# 05_Mechanical.net
KiCad netlist of a schematic drawn in Altium Designer
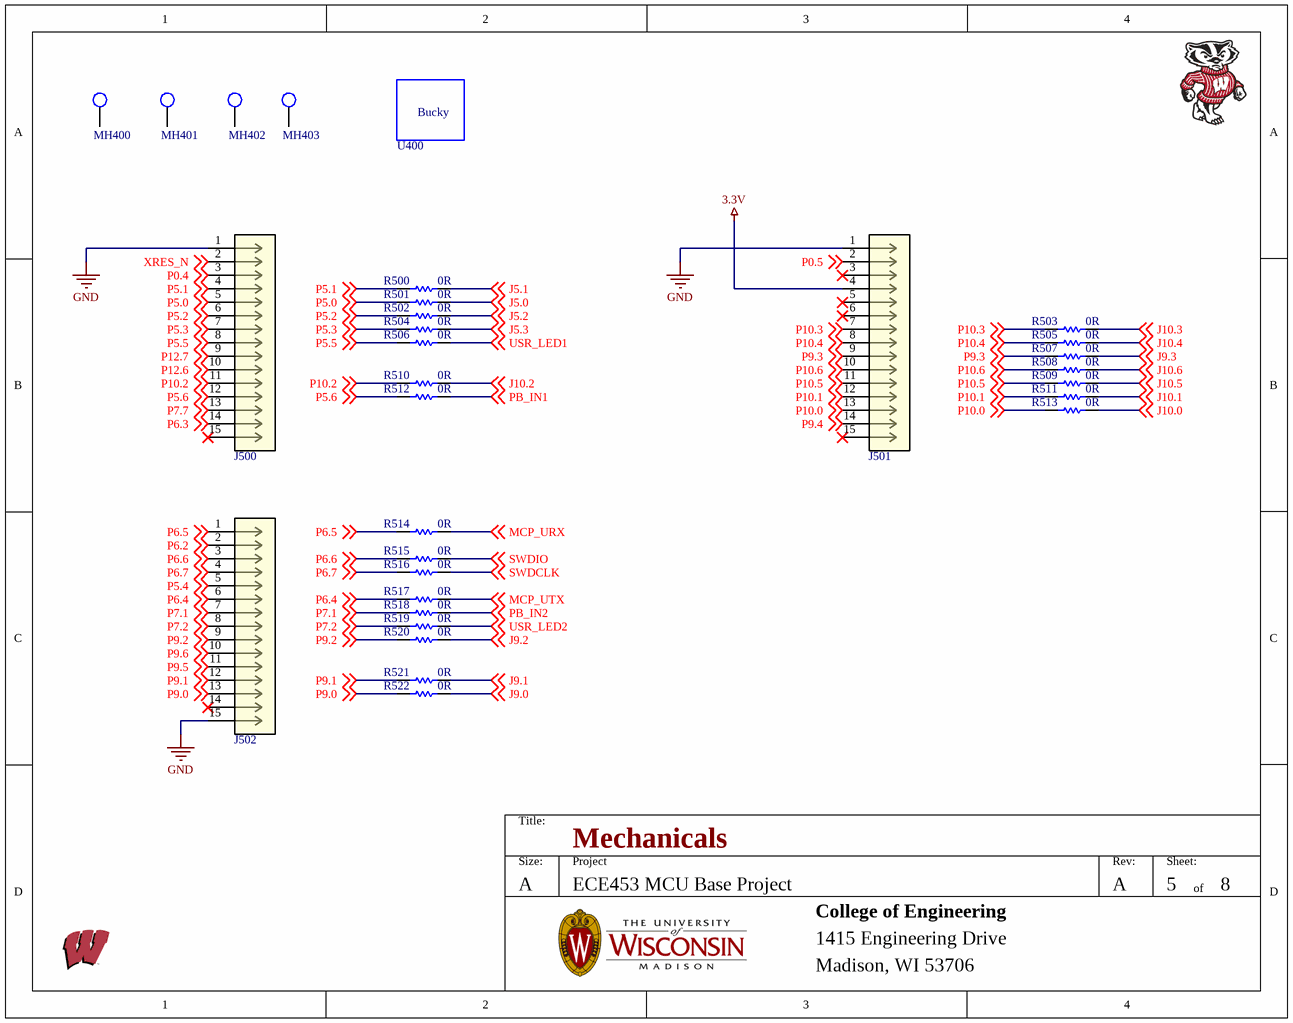
[diagram p0: 05_Mechanical.SchDoc]

(export (version "E")
  (design (tool "Eeschema 10.0.6"))
  (components
    (comp (ref "J500")
      (value "68000-115HLF")
      (footprint "CONN_15POS_2P54MM")
      (description "Conn Unshrouded Header HDR 15 POS 2.54mm Solder ST Thru-Hole")
      (fields
        (field (name "MANUFACTURER") "Adam Equipment")
        (field (name "MANUFACTURER PART NUMBER") "PH1-15-UA")
        (field (name "COPYRIGHT") "Copyright (C) 2024 Ultra Librarian. All rights reserved.")
      )
      (libsource (lib "ECE453_S24") (part "CONN_HEADER_POS_30_2.54MM"))
    )
    (comp (ref "J501")
      (value "68000-115HLF")
      (footprint "CONN_15POS_2P54MM")
      (description "Conn Unshrouded Header HDR 15 POS 2.54mm Solder ST Thru-Hole")
      (fields
        (field (name "MANUFACTURER") "Adam Equipment")
        (field (name "MANUFACTURER PART NUMBER") "PH1-15-UA")
        (field (name "COPYRIGHT") "Copyright (C) 2024 Ultra Librarian. All rights reserved.")
      )
      (libsource (lib "ECE453_S24") (part "CONN_HEADER_POS_30_2.54MM"))
    )
    (comp (ref "J502")
      (value "68000-115HLF")
      (footprint "CONN_15POS_2P54MM")
      (description "Conn Unshrouded Header HDR 15 POS 2.54mm Solder ST Thru-Hole")
      (fields
        (field (name "MANUFACTURER") "Adam Equipment")
        (field (name "MANUFACTURER PART NUMBER") "PH1-15-UA")
        (field (name "COPYRIGHT") "Copyright (C) 2024 Ultra Librarian. All rights reserved.")
      )
      (libsource (lib "ECE453_S24") (part "CONN_HEADER_POS_30_2.54MM"))
    )
    (comp (ref "MH400")
      (value "MHOLE_2_55MM")
      (footprint "MHOLE_2_55MM")
      (description "Mounting Holde")
      (fields (field (name "MANUFACTURER PART NUMBER") "UW MTHOLE"))
      (libsource (lib "ECE453_S24") (part "MHOLE_2_55MM"))
    )
    (comp (ref "MH401")
      (value "MHOLE_2_55MM")
      (footprint "MHOLE_2_55MM")
      (description "Mounting Holde")
      (fields (field (name "MANUFACTURER PART NUMBER") "UW MTHOLE"))
      (libsource (lib "ECE453_S24") (part "MHOLE_2_55MM"))
    )
    (comp (ref "MH402")
      (value "MHOLE_2_55MM")
      (footprint "MHOLE_2_55MM")
      (description "Mounting Holde")
      (fields (field (name "MANUFACTURER PART NUMBER") "UW MTHOLE"))
      (libsource (lib "ECE453_S24") (part "MHOLE_2_55MM"))
    )
    (comp (ref "MH403")
      (value "MHOLE_2_55MM")
      (footprint "MHOLE_2_55MM")
      (description "Mounting Holde")
      (fields (field (name "MANUFACTURER PART NUMBER") "UW MTHOLE"))
      (libsource (lib "ECE453_S24") (part "MHOLE_2_55MM"))
    )
    (comp (ref "R500")
      (value "0R")
      (footprint "RESC2013X70X40NL20T20")
      (description "Chip Resistor, 0 Ohm, +/- 1%, 0.125 W, -55 to 155 degC, 0805 (2012 Metric), RoHS, Tape and Reel")
      (fields (field (name "PARTNUMBER") "ERJ-6GEY0R00V") (field (name "TOLERANCE") "5%"))
      (libsource (lib "Altium Content Vault") (part "RES-2"))
    )
    (comp (ref "R501")
      (value "0R")
      (footprint "RESC2013X70X40NL20T20")
      (description "Chip Resistor, 0 Ohm, +/- 1%, 0.125 W, -55 to 155 degC, 0805 (2012 Metric), RoHS, Tape and Reel")
      (fields (field (name "PARTNUMBER") "ERJ-6GEY0R00V") (field (name "TOLERANCE") "5%"))
      (libsource (lib "Altium Content Vault") (part "RES-2"))
    )
    (comp (ref "R502")
      (value "0R")
      (footprint "RESC2013X70X40NL20T20")
      (description "Chip Resistor, 0 Ohm, +/- 1%, 0.125 W, -55 to 155 degC, 0805 (2012 Metric), RoHS, Tape and Reel")
      (fields (field (name "PARTNUMBER") "ERJ-6GEY0R00V") (field (name "TOLERANCE") "5%"))
      (libsource (lib "Altium Content Vault") (part "RES-2"))
    )
    (comp (ref "R503")
      (value "0R")
      (footprint "RESC2013X70X40NL20T20")
      (description "Chip Resistor, 0 Ohm, +/- 1%, 0.125 W, -55 to 155 degC, 0805 (2012 Metric), RoHS, Tape and Reel")
      (fields (field (name "PARTNUMBER") "ERJ-6GEY0R00V") (field (name "TOLERANCE") "5%"))
      (libsource (lib "Altium Content Vault") (part "RES-2"))
    )
    (comp (ref "R504")
      (value "0R")
      (footprint "RESC2013X70X40NL20T20")
      (description "Chip Resistor, 0 Ohm, +/- 1%, 0.125 W, -55 to 155 degC, 0805 (2012 Metric), RoHS, Tape and Reel")
      (fields (field (name "PARTNUMBER") "ERJ-6GEY0R00V") (field (name "TOLERANCE") "5%"))
      (libsource (lib "Altium Content Vault") (part "RES-2"))
    )
    (comp (ref "R505")
      (value "0R")
      (footprint "RESC2013X70X40NL20T20")
      (description "Chip Resistor, 0 Ohm, +/- 1%, 0.125 W, -55 to 155 degC, 0805 (2012 Metric), RoHS, Tape and Reel")
      (fields (field (name "PARTNUMBER") "ERJ-6GEY0R00V") (field (name "TOLERANCE") "5%"))
      (libsource (lib "Altium Content Vault") (part "RES-2"))
    )
    (comp (ref "R506")
      (value "0R")
      (footprint "RESC2013X70X40NL20T20")
      (description "Chip Resistor, 0 Ohm, +/- 1%, 0.125 W, -55 to 155 degC, 0805 (2012 Metric), RoHS, Tape and Reel")
      (fields (field (name "PARTNUMBER") "ERJ-6GEY0R00V") (field (name "TOLERANCE") "5%"))
      (libsource (lib "Altium Content Vault") (part "RES-2"))
    )
    (comp (ref "R507")
      (value "0R")
      (footprint "RESC2013X70X40NL20T20")
      (description "Chip Resistor, 0 Ohm, +/- 1%, 0.125 W, -55 to 155 degC, 0805 (2012 Metric), RoHS, Tape and Reel")
      (fields (field (name "PARTNUMBER") "ERJ-6GEY0R00V") (field (name "TOLERANCE") "5%"))
      (libsource (lib "Altium Content Vault") (part "RES-2"))
    )
    (comp (ref "R508")
      (value "0R")
      (footprint "RESC2013X70X40NL20T20")
      (description "Chip Resistor, 0 Ohm, +/- 1%, 0.125 W, -55 to 155 degC, 0805 (2012 Metric), RoHS, Tape and Reel")
      (fields (field (name "PARTNUMBER") "ERJ-6GEY0R00V") (field (name "TOLERANCE") "5%"))
      (libsource (lib "Altium Content Vault") (part "RES-2"))
    )
    (comp (ref "R509")
      (value "0R")
      (footprint "RESC2013X70X40NL20T20")
      (description "Chip Resistor, 0 Ohm, +/- 1%, 0.125 W, -55 to 155 degC, 0805 (2012 Metric), RoHS, Tape and Reel")
      (fields (field (name "PARTNUMBER") "ERJ-6GEY0R00V") (field (name "TOLERANCE") "5%"))
      (libsource (lib "Altium Content Vault") (part "RES-2"))
    )
    (comp (ref "R510")
      (value "0R")
      (footprint "RESC2013X70X40NL20T20")
      (description "Chip Resistor, 0 Ohm, +/- 1%, 0.125 W, -55 to 155 degC, 0805 (2012 Metric), RoHS, Tape and Reel")
      (fields (field (name "PARTNUMBER") "ERJ-6GEY0R00V") (field (name "TOLERANCE") "5%"))
      (libsource (lib "Altium Content Vault") (part "RES-2"))
    )
    (comp (ref "R511")
      (value "0R")
      (footprint "RESC2013X70X40NL20T20")
      (description "Chip Resistor, 0 Ohm, +/- 1%, 0.125 W, -55 to 155 degC, 0805 (2012 Metric), RoHS, Tape and Reel")
      (fields (field (name "PARTNUMBER") "ERJ-6GEY0R00V") (field (name "TOLERANCE") "5%"))
      (libsource (lib "Altium Content Vault") (part "RES-2"))
    )
    (comp (ref "R512")
      (value "0R")
      (footprint "RESC2013X70X40NL20T20")
      (description "Chip Resistor, 0 Ohm, +/- 1%, 0.125 W, -55 to 155 degC, 0805 (2012 Metric), RoHS, Tape and Reel")
      (fields (field (name "PARTNUMBER") "ERJ-6GEY0R00V") (field (name "TOLERANCE") "5%"))
      (libsource (lib "Altium Content Vault") (part "RES-2"))
    )
    (comp (ref "R513")
      (value "0R")
      (footprint "RESC2013X70X40NL20T20")
      (description "Chip Resistor, 0 Ohm, +/- 1%, 0.125 W, -55 to 155 degC, 0805 (2012 Metric), RoHS, Tape and Reel")
      (fields (field (name "PARTNUMBER") "ERJ-6GEY0R00V") (field (name "TOLERANCE") "5%"))
      (libsource (lib "Altium Content Vault") (part "RES-2"))
    )
    (comp (ref "R514")
      (value "0R")
      (footprint "RESC2013X70X40NL20T20")
      (description "Chip Resistor, 0 Ohm, +/- 1%, 0.125 W, -55 to 155 degC, 0805 (2012 Metric), RoHS, Tape and Reel")
      (fields (field (name "PARTNUMBER") "ERJ-6GEY0R00V") (field (name "TOLERANCE") "5%"))
      (libsource (lib "Altium Content Vault") (part "RES-2"))
    )
    (comp (ref "R515")
      (value "0R")
      (footprint "RESC2013X70X40NL20T20")
      (description "Chip Resistor, 0 Ohm, +/- 1%, 0.125 W, -55 to 155 degC, 0805 (2012 Metric), RoHS, Tape and Reel")
      (fields (field (name "PARTNUMBER") "ERJ-6GEY0R00V") (field (name "TOLERANCE") "5%"))
      (libsource (lib "Altium Content Vault") (part "RES-2"))
    )
    (comp (ref "R516")
      (value "0R")
      (footprint "RESC2013X70X40NL20T20")
      (description "Chip Resistor, 0 Ohm, +/- 1%, 0.125 W, -55 to 155 degC, 0805 (2012 Metric), RoHS, Tape and Reel")
      (fields (field (name "PARTNUMBER") "ERJ-6GEY0R00V") (field (name "TOLERANCE") "5%"))
      (libsource (lib "Altium Content Vault") (part "RES-2"))
    )
    (comp (ref "R517")
      (value "0R")
      (footprint "RESC2013X70X40NL20T20")
      (description "Chip Resistor, 0 Ohm, +/- 1%, 0.125 W, -55 to 155 degC, 0805 (2012 Metric), RoHS, Tape and Reel")
      (fields (field (name "PARTNUMBER") "ERJ-6GEY0R00V") (field (name "TOLERANCE") "5%"))
      (libsource (lib "Altium Content Vault") (part "RES-2"))
    )
    (comp (ref "R518")
      (value "0R")
      (footprint "RESC2013X70X40NL20T20")
      (description "Chip Resistor, 0 Ohm, +/- 1%, 0.125 W, -55 to 155 degC, 0805 (2012 Metric), RoHS, Tape and Reel")
      (fields (field (name "PARTNUMBER") "ERJ-6GEY0R00V") (field (name "TOLERANCE") "5%"))
      (libsource (lib "Altium Content Vault") (part "RES-2"))
    )
    (comp (ref "R519")
      (value "0R")
      (footprint "RESC2013X70X40NL20T20")
      (description "Chip Resistor, 0 Ohm, +/- 1%, 0.125 W, -55 to 155 degC, 0805 (2012 Metric), RoHS, Tape and Reel")
      (fields (field (name "PARTNUMBER") "ERJ-6GEY0R00V") (field (name "TOLERANCE") "5%"))
      (libsource (lib "Altium Content Vault") (part "RES-2"))
    )
    (comp (ref "R520")
      (value "0R")
      (footprint "RESC2013X70X40NL20T20")
      (description "Chip Resistor, 0 Ohm, +/- 1%, 0.125 W, -55 to 155 degC, 0805 (2012 Metric), RoHS, Tape and Reel")
      (fields (field (name "PARTNUMBER") "ERJ-6GEY0R00V") (field (name "TOLERANCE") "5%"))
      (libsource (lib "Altium Content Vault") (part "RES-2"))
    )
    (comp (ref "R521")
      (value "0R")
      (footprint "RESC2013X70X40NL20T20")
      (description "Chip Resistor, 0 Ohm, +/- 1%, 0.125 W, -55 to 155 degC, 0805 (2012 Metric), RoHS, Tape and Reel")
      (fields (field (name "PARTNUMBER") "ERJ-6GEY0R00V") (field (name "TOLERANCE") "5%"))
      (libsource (lib "Altium Content Vault") (part "RES-2"))
    )
    (comp (ref "R522")
      (value "0R")
      (footprint "RESC2013X70X40NL20T20")
      (description "Chip Resistor, 0 Ohm, +/- 1%, 0.125 W, -55 to 155 degC, 0805 (2012 Metric), RoHS, Tape and Reel")
      (fields (field (name "PARTNUMBER") "ERJ-6GEY0R00V") (field (name "TOLERANCE") "5%"))
      (libsource (lib "Altium Content Vault") (part "RES-2"))
    )
    (comp (ref "U400")
      (value "Bucky")
      (footprint "WalkingBucky")
      (description "Bucky Badger Image")
      (fields (field (name "MANUFACTURER PART NUMBER") "UW Bucky"))
      (libsource (lib "ECE453") (part "Bucky"))
    )
  )
  (nets
    (net (code "1") (name "3.3V") (class "Default")
      (node (ref "J501") (pin "4") (pinfunction "4_4") (pintype "passive"))
    )
    (net (code "2") (name "GND") (class "Default")
      (node (ref "J500") (pin "1") (pinfunction "1_1") (pintype "passive"))
      (node (ref "J501") (pin "1") (pinfunction "1_1") (pintype "passive"))
      (node (ref "J502") (pin "15") (pinfunction "15_15") (pintype "passive"))
    )
    (net (code "3") (name "J5.0") (class "Default")
      (node (ref "R501") (pin "2") (pinfunction "2_2") (pintype "passive"))
    )
    (net (code "4") (name "J5.1") (class "Default")
      (node (ref "R500") (pin "2") (pinfunction "2_2") (pintype "passive"))
    )
    (net (code "5") (name "J5.2") (class "Default")
      (node (ref "R502") (pin "2") (pinfunction "2_2") (pintype "passive"))
    )
    (net (code "6") (name "J5.3") (class "Default")
      (node (ref "R504") (pin "2") (pinfunction "2_2") (pintype "passive"))
    )
    (net (code "7") (name "J9.0") (class "Default")
      (node (ref "R522") (pin "2") (pinfunction "2_2") (pintype "passive"))
    )
    (net (code "8") (name "J9.1") (class "Default")
      (node (ref "R521") (pin "2") (pinfunction "2_2") (pintype "passive"))
    )
    (net (code "9") (name "J9.2") (class "Default")
      (node (ref "R520") (pin "2") (pinfunction "2_2") (pintype "passive"))
    )
    (net (code "10") (name "J9.3") (class "Default")
      (node (ref "R507") (pin "2") (pinfunction "2_2") (pintype "passive"))
    )
    (net (code "11") (name "J10.0") (class "Default")
      (node (ref "R513") (pin "2") (pinfunction "2_2") (pintype "passive"))
    )
    (net (code "12") (name "J10.1") (class "Default")
      (node (ref "R511") (pin "2") (pinfunction "2_2") (pintype "passive"))
    )
    (net (code "13") (name "J10.2") (class "Default")
      (node (ref "R510") (pin "2") (pinfunction "2_2") (pintype "passive"))
    )
    (net (code "14") (name "J10.3") (class "Default")
      (node (ref "R503") (pin "2") (pinfunction "2_2") (pintype "passive"))
    )
    (net (code "15") (name "J10.4") (class "Default")
      (node (ref "R505") (pin "2") (pinfunction "2_2") (pintype "passive"))
    )
    (net (code "16") (name "J10.5") (class "Default")
      (node (ref "R509") (pin "2") (pinfunction "2_2") (pintype "passive"))
    )
    (net (code "17") (name "J10.6") (class "Default")
      (node (ref "R508") (pin "2") (pinfunction "2_2") (pintype "passive"))
    )
    (net (code "18") (name "MCP_URX") (class "Default")
      (node (ref "R514") (pin "2") (pinfunction "2_2") (pintype "passive"))
    )
    (net (code "19") (name "MCP_UTX") (class "Default")
      (node (ref "R517") (pin "2") (pinfunction "2_2") (pintype "passive"))
    )
    (net (code "20") (name "P0.4") (class "Default")
      (node (ref "J500") (pin "3") (pinfunction "3_3") (pintype "passive"))
    )
    (net (code "21") (name "P0.5") (class "Default")
      (node (ref "J501") (pin "2") (pinfunction "2_2") (pintype "passive"))
    )
    (net (code "22") (name "P5.0") (class "Default")
      (node (ref "J500") (pin "5") (pinfunction "5_5") (pintype "passive"))
      (node (ref "R501") (pin "1") (pinfunction "1_1") (pintype "passive"))
    )
    (net (code "23") (name "P5.1") (class "Default")
      (node (ref "J500") (pin "4") (pinfunction "4_4") (pintype "passive"))
      (node (ref "R500") (pin "1") (pinfunction "1_1") (pintype "passive"))
    )
    (net (code "24") (name "P5.2") (class "Default")
      (node (ref "J500") (pin "6") (pinfunction "6_6") (pintype "passive"))
      (node (ref "R502") (pin "1") (pinfunction "1_1") (pintype "passive"))
    )
    (net (code "25") (name "P5.3") (class "Default")
      (node (ref "J500") (pin "7") (pinfunction "7_7") (pintype "passive"))
      (node (ref "R504") (pin "1") (pinfunction "1_1") (pintype "passive"))
    )
    (net (code "26") (name "P5.4") (class "Default")
      (node (ref "J502") (pin "5") (pinfunction "5_5") (pintype "passive"))
    )
    (net (code "27") (name "P5.5") (class "Default")
      (node (ref "J500") (pin "8") (pinfunction "8_8") (pintype "passive"))
      (node (ref "R506") (pin "1") (pinfunction "1_1") (pintype "passive"))
    )
    (net (code "28") (name "P5.6") (class "Default")
      (node (ref "J500") (pin "12") (pinfunction "12_12") (pintype "passive"))
      (node (ref "R512") (pin "1") (pinfunction "1_1") (pintype "passive"))
    )
    (net (code "29") (name "P6.2") (class "Default")
      (node (ref "J502") (pin "2") (pinfunction "2_2") (pintype "passive"))
    )
    (net (code "30") (name "P6.3") (class "Default")
      (node (ref "J500") (pin "14") (pinfunction "14_14") (pintype "passive"))
    )
    (net (code "31") (name "P6.4") (class "Default")
      (node (ref "J502") (pin "6") (pinfunction "6_6") (pintype "passive"))
      (node (ref "R517") (pin "1") (pinfunction "1_1") (pintype "passive"))
    )
    (net (code "32") (name "P6.5") (class "Default")
      (node (ref "J502") (pin "1") (pinfunction "1_1") (pintype "passive"))
      (node (ref "R514") (pin "1") (pinfunction "1_1") (pintype "passive"))
    )
    (net (code "33") (name "P6.6") (class "Default")
      (node (ref "J502") (pin "3") (pinfunction "3_3") (pintype "passive"))
      (node (ref "R515") (pin "1") (pinfunction "1_1") (pintype "passive"))
    )
    (net (code "34") (name "P6.7") (class "Default")
      (node (ref "J502") (pin "4") (pinfunction "4_4") (pintype "passive"))
      (node (ref "R516") (pin "1") (pinfunction "1_1") (pintype "passive"))
    )
    (net (code "35") (name "P7.1") (class "Default")
      (node (ref "J502") (pin "7") (pinfunction "7_7") (pintype "passive"))
      (node (ref "R518") (pin "1") (pinfunction "1_1") (pintype "passive"))
    )
    (net (code "36") (name "P7.2") (class "Default")
      (node (ref "J502") (pin "8") (pinfunction "8_8") (pintype "passive"))
      (node (ref "R519") (pin "1") (pinfunction "1_1") (pintype "passive"))
    )
    (net (code "37") (name "P7.7") (class "Default")
      (node (ref "J500") (pin "13") (pinfunction "13_13") (pintype "passive"))
    )
    (net (code "38") (name "P9.0") (class "Default")
      (node (ref "J502") (pin "13") (pinfunction "13_13") (pintype "passive"))
      (node (ref "R522") (pin "1") (pinfunction "1_1") (pintype "passive"))
    )
    (net (code "39") (name "P9.1") (class "Default")
      (node (ref "J502") (pin "12") (pinfunction "12_12") (pintype "passive"))
      (node (ref "R521") (pin "1") (pinfunction "1_1") (pintype "passive"))
    )
    (net (code "40") (name "P9.2") (class "Default")
      (node (ref "J502") (pin "9") (pinfunction "9_9") (pintype "passive"))
      (node (ref "R520") (pin "1") (pinfunction "1_1") (pintype "passive"))
    )
    (net (code "41") (name "P9.3") (class "Default")
      (node (ref "J501") (pin "9") (pinfunction "9_9") (pintype "passive"))
      (node (ref "R507") (pin "1") (pinfunction "1_1") (pintype "passive"))
    )
    (net (code "42") (name "P9.4") (class "Default")
      (node (ref "J501") (pin "14") (pinfunction "14_14") (pintype "passive"))
    )
    (net (code "43") (name "P9.5") (class "Default")
      (node (ref "J502") (pin "11") (pinfunction "11_11") (pintype "passive"))
    )
    (net (code "44") (name "P9.6") (class "Default")
      (node (ref "J502") (pin "10") (pinfunction "10_10") (pintype "passive"))
    )
    (net (code "45") (name "P10.0") (class "Default")
      (node (ref "J501") (pin "13") (pinfunction "13_13") (pintype "passive"))
      (node (ref "R513") (pin "1") (pinfunction "1_1") (pintype "passive"))
    )
    (net (code "46") (name "P10.1") (class "Default")
      (node (ref "J501") (pin "12") (pinfunction "12_12") (pintype "passive"))
      (node (ref "R511") (pin "1") (pinfunction "1_1") (pintype "passive"))
    )
    (net (code "47") (name "P10.2") (class "Default")
      (node (ref "J500") (pin "11") (pinfunction "11_11") (pintype "passive"))
      (node (ref "R510") (pin "1") (pinfunction "1_1") (pintype "passive"))
    )
    (net (code "48") (name "P10.3") (class "Default")
      (node (ref "J501") (pin "7") (pinfunction "7_7") (pintype "passive"))
      (node (ref "R503") (pin "1") (pinfunction "1_1") (pintype "passive"))
    )
    (net (code "49") (name "P10.4") (class "Default")
      (node (ref "J501") (pin "8") (pinfunction "8_8") (pintype "passive"))
      (node (ref "R505") (pin "1") (pinfunction "1_1") (pintype "passive"))
    )
    (net (code "50") (name "P10.5") (class "Default")
      (node (ref "J501") (pin "11") (pinfunction "11_11") (pintype "passive"))
      (node (ref "R509") (pin "1") (pinfunction "1_1") (pintype "passive"))
    )
    (net (code "51") (name "P10.6") (class "Default")
      (node (ref "J501") (pin "10") (pinfunction "10_10") (pintype "passive"))
      (node (ref "R508") (pin "1") (pinfunction "1_1") (pintype "passive"))
    )
    (net (code "52") (name "P12.6") (class "Default")
      (node (ref "J500") (pin "10") (pinfunction "10_10") (pintype "passive"))
    )
    (net (code "53") (name "P12.7") (class "Default")
      (node (ref "J500") (pin "9") (pinfunction "9_9") (pintype "passive"))
    )
    (net (code "54") (name "PB_IN1") (class "Default")
      (node (ref "R512") (pin "2") (pinfunction "2_2") (pintype "passive"))
    )
    (net (code "55") (name "PB_IN2") (class "Default")
      (node (ref "R518") (pin "2") (pinfunction "2_2") (pintype "passive"))
    )
    (net (code "56") (name "SWDCLK") (class "Default")
      (node (ref "R516") (pin "2") (pinfunction "2_2") (pintype "passive"))
    )
    (net (code "57") (name "SWDIO") (class "Default")
      (node (ref "R515") (pin "2") (pinfunction "2_2") (pintype "passive"))
    )
    (net (code "58") (name "USR_LED1") (class "Default")
      (node (ref "R506") (pin "2") (pinfunction "2_2") (pintype "passive"))
    )
    (net (code "59") (name "USR_LED2") (class "Default")
      (node (ref "R519") (pin "2") (pinfunction "2_2") (pintype "passive"))
    )
    (net (code "60") (name "XRES_N") (class "Default")
      (node (ref "J500") (pin "2") (pinfunction "2_2") (pintype "passive"))
    )
    (net (code "61") (name "unconnected-(J500-Pad15)") (class "Default")
      (node (ref "J500") (pin "15") (pinfunction "15_15") (pintype "passive+no_connect"))
    )
    (net (code "62") (name "unconnected-(J501-Pad3)") (class "Default")
      (node (ref "J501") (pin "3") (pinfunction "3_3") (pintype "passive+no_connect"))
    )
    (net (code "63") (name "unconnected-(J501-Pad5)") (class "Default")
      (node (ref "J501") (pin "5") (pinfunction "5_5") (pintype "passive+no_connect"))
    )
    (net (code "64") (name "unconnected-(J501-Pad6)") (class "Default")
      (node (ref "J501") (pin "6") (pinfunction "6_6") (pintype "passive+no_connect"))
    )
    (net (code "65") (name "unconnected-(J501-Pad15)") (class "Default")
      (node (ref "J501") (pin "15") (pinfunction "15_15") (pintype "passive+no_connect"))
    )
    (net (code "66") (name "unconnected-(J502-Pad14)") (class "Default")
      (node (ref "J502") (pin "14") (pinfunction "14_14") (pintype "passive+no_connect"))
    )
    (net (code "67") (name "unconnected-(MH400-Pad1)") (class "Default")
      (node (ref "MH400") (pin "1") (pintype "passive"))
    )
    (net (code "68") (name "unconnected-(MH401-Pad1)") (class "Default")
      (node (ref "MH401") (pin "1") (pintype "passive"))
    )
    (net (code "69") (name "unconnected-(MH402-Pad1)") (class "Default")
      (node (ref "MH402") (pin "1") (pintype "passive"))
    )
    (net (code "70") (name "unconnected-(MH403-Pad1)") (class "Default")
      (node (ref "MH403") (pin "1") (pintype "passive"))
    )
  )
)
